# pcb.net
KiCad netlist of a schematic drawn in EAGLE
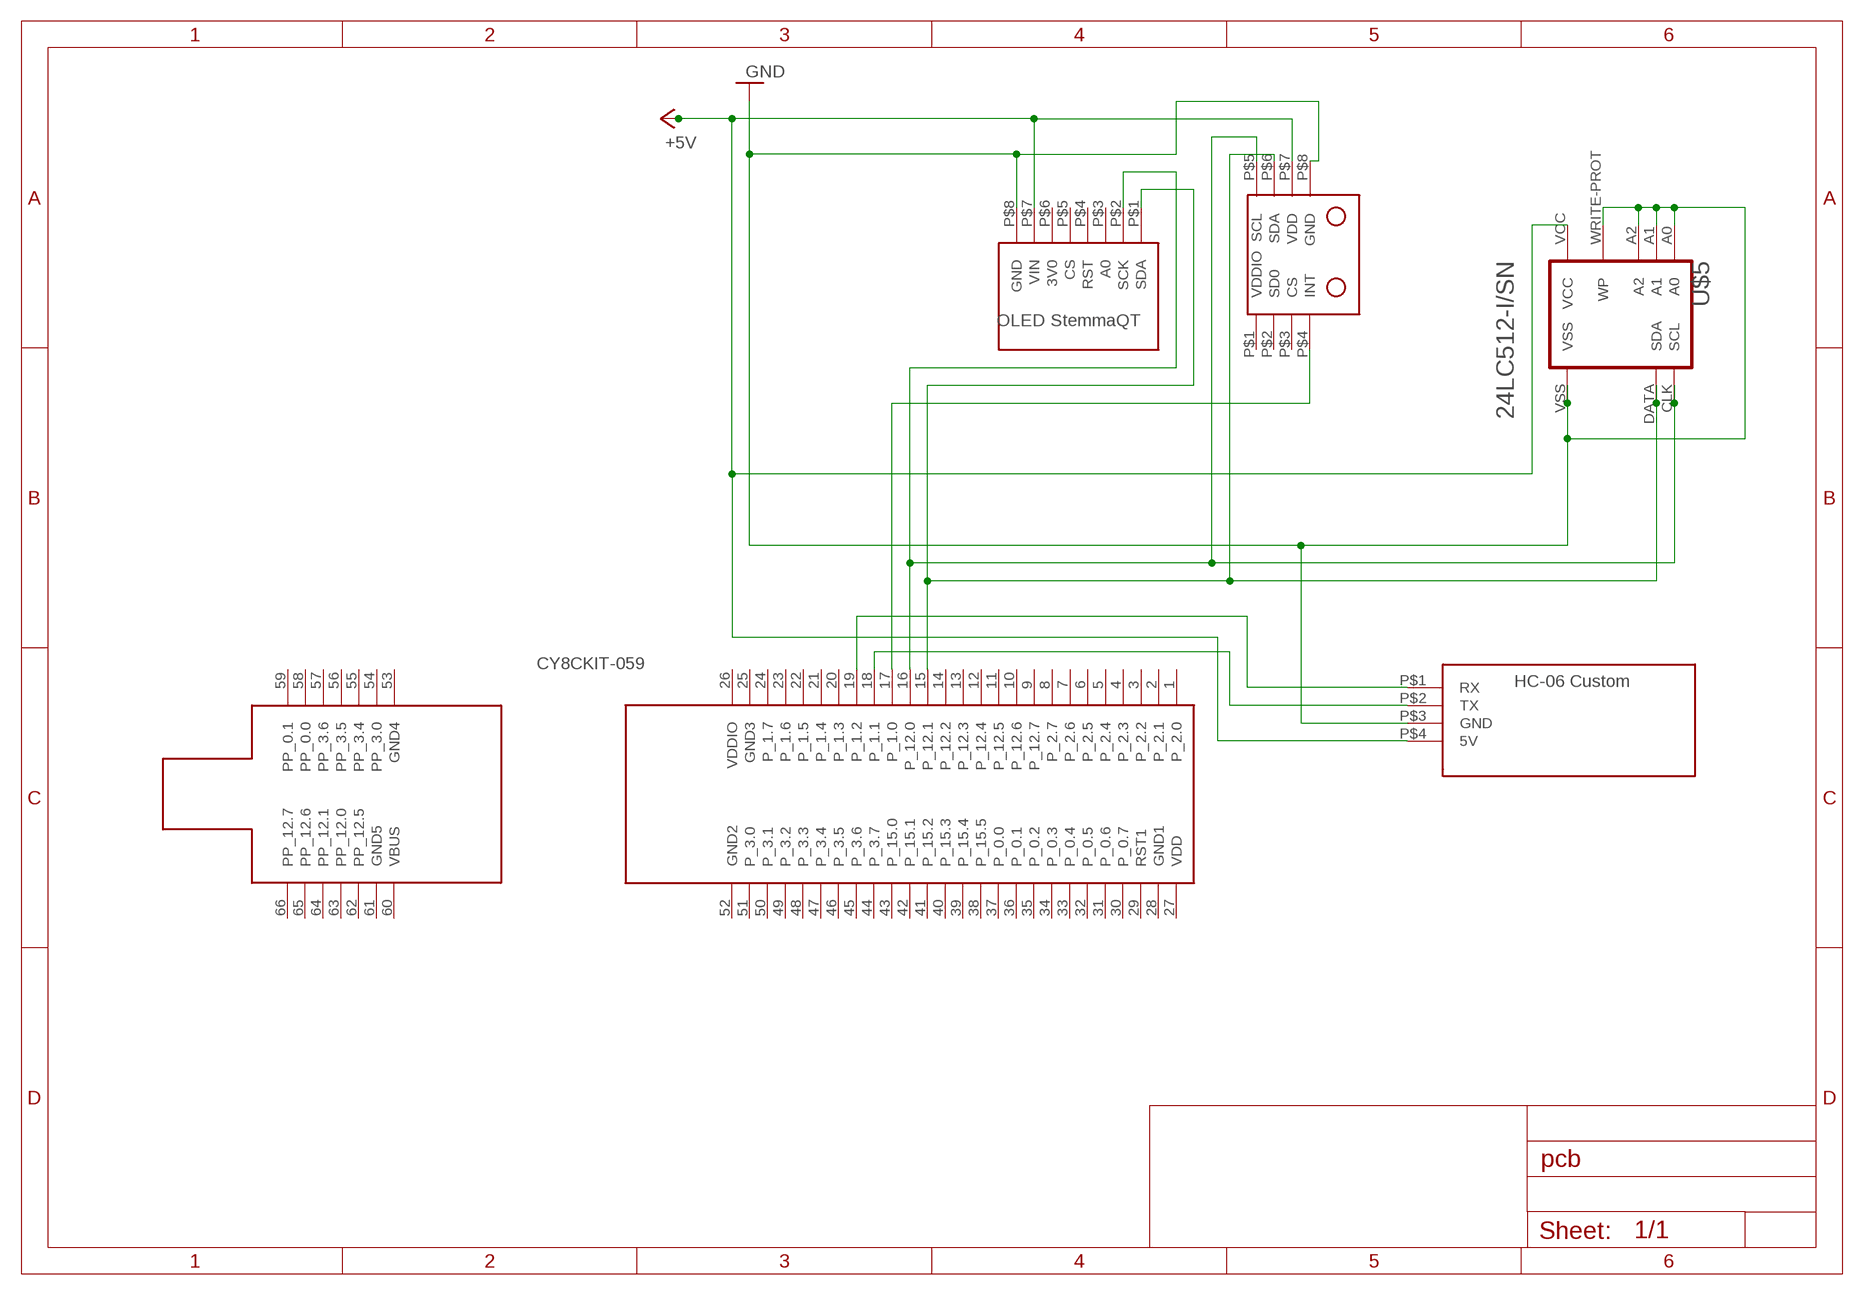
[diagram p0: schematic, sheet 1]

(export (version "E")
  (design (tool "Eeschema 10.0.6"))
  (components
    (comp (ref "U$1")
      (value "CY8CKIT-059")
      (footprint "eagle-import:CY8CKIT-059")
      (libsource (lib "eagle-import") (part "CY8CKIT-059"))
    )
    (comp (ref "U$2")
      (value "SSD1306_STEMMAQT_128X64")
      (footprint "eagle-import:FTP_SSD1306_128X64_4PIN")
      (libsource (lib "eagle-import") (part "SSD1306_STEMMAQT_128X64"))
    )
    (comp (ref "U$3")
      (value "HC-06_CUSTOM")
      (footprint "eagle-import:FTP_HC-06_CUSTOM")
      (libsource (lib "eagle-import") (part "HC-06_CUSTOM"))
    )
    (comp (ref "U$4")
      (value "MPU9250")
      (footprint "eagle-import:FTP_MPU9650")
      (libsource (lib "eagle-import") (part "MPU9250"))
    )
    (comp (ref "U$5")
      (value "24LC512-I-CUSTOM")
      (footprint "eagle-import:24LC512-I-CUSTOM")
      (libsource (lib "eagle-import") (part "24LC512-I-CUSTOM"))
    )
  )
  (nets
    (net (code "1") (name "+5V") (class "Default")
      (node (ref "U$2") (pin "P$7") (pinfunction "VIN_P$7") (pintype "bidirectional"))
      (node (ref "U$3") (pin "P$4") (pinfunction "5V_P$4") (pintype "bidirectional"))
      (node (ref "U$4") (pin "P$7") (pinfunction "VDD_P$7") (pintype "bidirectional"))
      (node (ref "U$5") (pin "VCC") (pinfunction "VCC_VCC") (pintype "power_in"))
    )
    (net (code "2") (name "GND") (class "Default")
      (node (ref "U$2") (pin "P$8") (pinfunction "GND_P$8") (pintype "bidirectional"))
      (node (ref "U$3") (pin "P$3") (pinfunction "GND_P$3") (pintype "bidirectional"))
      (node (ref "U$4") (pin "P$8") (pinfunction "GND_P$8") (pintype "bidirectional"))
      (node (ref "U$5") (pin "A0") (pinfunction "A0_A0") (pintype "input"))
      (node (ref "U$5") (pin "A1") (pinfunction "A1_A1") (pintype "input"))
      (node (ref "U$5") (pin "A2") (pinfunction "A2_A2") (pintype "input"))
      (node (ref "U$5") (pin "VSS") (pinfunction "VSS_VSS") (pintype "power_in"))
      (node (ref "U$5") (pin "WRITE-PROT") (pinfunction "WP_WRITE-PROT") (pintype "input"))
    )
    (net (code "3") (name "Net-(U$1-P_1.0)") (class "Default")
      (node (ref "U$1") (pin "17") (pinfunction "P_1.0_17") (pintype "bidirectional"))
      (node (ref "U$4") (pin "P$4") (pinfunction "INT_P$4") (pintype "bidirectional"))
    )
    (net (code "4") (name "Net-(U$1-P_1.1)") (class "Default")
      (node (ref "U$1") (pin "18") (pinfunction "P_1.1_18") (pintype "bidirectional"))
      (node (ref "U$3") (pin "P$2") (pinfunction "TX_P$2") (pintype "bidirectional"))
    )
    (net (code "5") (name "Net-(U$1-P_1.2)") (class "Default")
      (node (ref "U$1") (pin "19") (pinfunction "P_1.2_19") (pintype "bidirectional"))
      (node (ref "U$3") (pin "P$1") (pinfunction "RX_P$1") (pintype "bidirectional"))
    )
    (net (code "6") (name "Net-(U$1-P_12.0)") (class "Default")
      (node (ref "U$1") (pin "16") (pinfunction "P_12.0_16") (pintype "bidirectional"))
      (node (ref "U$2") (pin "P$2") (pinfunction "SCK_P$2") (pintype "bidirectional"))
      (node (ref "U$4") (pin "P$5") (pinfunction "SCL_P$5") (pintype "bidirectional"))
      (node (ref "U$5") (pin "CLK") (pinfunction "SCL_CLK") (pintype "input"))
    )
    (net (code "7") (name "Net-(U$1-P_12.1)") (class "Default")
      (node (ref "U$1") (pin "15") (pinfunction "P_12.1_15") (pintype "bidirectional"))
      (node (ref "U$2") (pin "P$1") (pinfunction "SDA_P$1") (pintype "bidirectional"))
      (node (ref "U$4") (pin "P$6") (pinfunction "SDA_P$6") (pintype "bidirectional"))
      (node (ref "U$5") (pin "DATA") (pinfunction "SDA_DATA") (pintype "bidirectional"))
    )
    (net (code "8") (name "unconnected-(U$1-GND1-Pad28)") (class "Default")
      (node (ref "U$1") (pin "28") (pinfunction "GND1_28") (pintype "bidirectional"))
    )
    (net (code "9") (name "unconnected-(U$1-GND2-Pad52)") (class "Default")
      (node (ref "U$1") (pin "52") (pinfunction "GND2_52") (pintype "bidirectional"))
    )
    (net (code "10") (name "unconnected-(U$1-GND3-Pad25)") (class "Default")
      (node (ref "U$1") (pin "25") (pinfunction "GND3_25") (pintype "bidirectional"))
    )
    (net (code "11") (name "unconnected-(U$1-GND4-Pad53)") (class "Default")
      (node (ref "U$1") (pin "53") (pinfunction "GND4_53") (pintype "bidirectional"))
    )
    (net (code "12") (name "unconnected-(U$1-GND5-Pad61)") (class "Default")
      (node (ref "U$1") (pin "61") (pinfunction "GND5_61") (pintype "bidirectional"))
    )
    (net (code "13") (name "unconnected-(U$1-PP_0.0-Pad58)") (class "Default")
      (node (ref "U$1") (pin "58") (pinfunction "PP_0.0_58") (pintype "bidirectional"))
    )
    (net (code "14") (name "unconnected-(U$1-PP_0.1-Pad59)") (class "Default")
      (node (ref "U$1") (pin "59") (pinfunction "PP_0.1_59") (pintype "bidirectional"))
    )
    (net (code "15") (name "unconnected-(U$1-PP_3.0-Pad54)") (class "Default")
      (node (ref "U$1") (pin "54") (pinfunction "PP_3.0_54") (pintype "bidirectional"))
    )
    (net (code "16") (name "unconnected-(U$1-PP_3.4-Pad55)") (class "Default")
      (node (ref "U$1") (pin "55") (pinfunction "PP_3.4_55") (pintype "bidirectional"))
    )
    (net (code "17") (name "unconnected-(U$1-PP_3.5-Pad56)") (class "Default")
      (node (ref "U$1") (pin "56") (pinfunction "PP_3.5_56") (pintype "bidirectional"))
    )
    (net (code "18") (name "unconnected-(U$1-PP_3.6-Pad57)") (class "Default")
      (node (ref "U$1") (pin "57") (pinfunction "PP_3.6_57") (pintype "bidirectional"))
    )
    (net (code "19") (name "unconnected-(U$1-PP_12.0-Pad63)") (class "Default")
      (node (ref "U$1") (pin "63") (pinfunction "PP_12.0_63") (pintype "bidirectional"))
    )
    (net (code "20") (name "unconnected-(U$1-PP_12.1-Pad64)") (class "Default")
      (node (ref "U$1") (pin "64") (pinfunction "PP_12.1_64") (pintype "bidirectional"))
    )
    (net (code "21") (name "unconnected-(U$1-PP_12.5-Pad62)") (class "Default")
      (node (ref "U$1") (pin "62") (pinfunction "PP_12.5_62") (pintype "bidirectional"))
    )
    (net (code "22") (name "unconnected-(U$1-PP_12.6-Pad65)") (class "Default")
      (node (ref "U$1") (pin "65") (pinfunction "PP_12.6_65") (pintype "bidirectional"))
    )
    (net (code "23") (name "unconnected-(U$1-PP_12.7-Pad66)") (class "Default")
      (node (ref "U$1") (pin "66") (pinfunction "PP_12.7_66") (pintype "bidirectional"))
    )
    (net (code "24") (name "unconnected-(U$1-P_0.0-Pad37)") (class "Default")
      (node (ref "U$1") (pin "37") (pinfunction "P_0.0_37") (pintype "bidirectional"))
    )
    (net (code "25") (name "unconnected-(U$1-P_0.1-Pad36)") (class "Default")
      (node (ref "U$1") (pin "36") (pinfunction "P_0.1_36") (pintype "bidirectional"))
    )
    (net (code "26") (name "unconnected-(U$1-P_0.2-Pad35)") (class "Default")
      (node (ref "U$1") (pin "35") (pinfunction "P_0.2_35") (pintype "bidirectional"))
    )
    (net (code "27") (name "unconnected-(U$1-P_0.3-Pad34)") (class "Default")
      (node (ref "U$1") (pin "34") (pinfunction "P_0.3_34") (pintype "bidirectional"))
    )
    (net (code "28") (name "unconnected-(U$1-P_0.4-Pad33)") (class "Default")
      (node (ref "U$1") (pin "33") (pinfunction "P_0.4_33") (pintype "bidirectional"))
    )
    (net (code "29") (name "unconnected-(U$1-P_0.5-Pad32)") (class "Default")
      (node (ref "U$1") (pin "32") (pinfunction "P_0.5_32") (pintype "bidirectional"))
    )
    (net (code "30") (name "unconnected-(U$1-P_0.6-Pad31)") (class "Default")
      (node (ref "U$1") (pin "31") (pinfunction "P_0.6_31") (pintype "bidirectional"))
    )
    (net (code "31") (name "unconnected-(U$1-P_0.7-Pad30)") (class "Default")
      (node (ref "U$1") (pin "30") (pinfunction "P_0.7_30") (pintype "bidirectional"))
    )
    (net (code "32") (name "unconnected-(U$1-P_1.3-Pad20)") (class "Default")
      (node (ref "U$1") (pin "20") (pinfunction "P_1.3_20") (pintype "bidirectional"))
    )
    (net (code "33") (name "unconnected-(U$1-P_1.4-Pad21)") (class "Default")
      (node (ref "U$1") (pin "21") (pinfunction "P_1.4_21") (pintype "bidirectional"))
    )
    (net (code "34") (name "unconnected-(U$1-P_1.5-Pad22)") (class "Default")
      (node (ref "U$1") (pin "22") (pinfunction "P_1.5_22") (pintype "bidirectional"))
    )
    (net (code "35") (name "unconnected-(U$1-P_1.6-Pad23)") (class "Default")
      (node (ref "U$1") (pin "23") (pinfunction "P_1.6_23") (pintype "bidirectional"))
    )
    (net (code "36") (name "unconnected-(U$1-P_1.7-Pad24)") (class "Default")
      (node (ref "U$1") (pin "24") (pinfunction "P_1.7_24") (pintype "bidirectional"))
    )
    (net (code "37") (name "unconnected-(U$1-P_2.0-Pad1)") (class "Default")
      (node (ref "U$1") (pin "1") (pinfunction "P_2.0_1") (pintype "bidirectional"))
    )
    (net (code "38") (name "unconnected-(U$1-P_2.1-Pad2)") (class "Default")
      (node (ref "U$1") (pin "2") (pinfunction "P_2.1_2") (pintype "bidirectional"))
    )
    (net (code "39") (name "unconnected-(U$1-P_2.2-Pad3)") (class "Default")
      (node (ref "U$1") (pin "3") (pinfunction "P_2.2_3") (pintype "bidirectional"))
    )
    (net (code "40") (name "unconnected-(U$1-P_2.3-Pad4)") (class "Default")
      (node (ref "U$1") (pin "4") (pinfunction "P_2.3_4") (pintype "bidirectional"))
    )
    (net (code "41") (name "unconnected-(U$1-P_2.4-Pad5)") (class "Default")
      (node (ref "U$1") (pin "5") (pinfunction "P_2.4_5") (pintype "bidirectional"))
    )
    (net (code "42") (name "unconnected-(U$1-P_2.5-Pad6)") (class "Default")
      (node (ref "U$1") (pin "6") (pinfunction "P_2.5_6") (pintype "bidirectional"))
    )
    (net (code "43") (name "unconnected-(U$1-P_2.6-Pad7)") (class "Default")
      (node (ref "U$1") (pin "7") (pinfunction "P_2.6_7") (pintype "bidirectional"))
    )
    (net (code "44") (name "unconnected-(U$1-P_2.7-Pad8)") (class "Default")
      (node (ref "U$1") (pin "8") (pinfunction "P_2.7_8") (pintype "bidirectional"))
    )
    (net (code "45") (name "unconnected-(U$1-P_3.0-Pad51)") (class "Default")
      (node (ref "U$1") (pin "51") (pinfunction "P_3.0_51") (pintype "bidirectional"))
    )
    (net (code "46") (name "unconnected-(U$1-P_3.1-Pad50)") (class "Default")
      (node (ref "U$1") (pin "50") (pinfunction "P_3.1_50") (pintype "bidirectional"))
    )
    (net (code "47") (name "unconnected-(U$1-P_3.2-Pad49)") (class "Default")
      (node (ref "U$1") (pin "49") (pinfunction "P_3.2_49") (pintype "bidirectional"))
    )
    (net (code "48") (name "unconnected-(U$1-P_3.3-Pad48)") (class "Default")
      (node (ref "U$1") (pin "48") (pinfunction "P_3.3_48") (pintype "bidirectional"))
    )
    (net (code "49") (name "unconnected-(U$1-P_3.4-Pad47)") (class "Default")
      (node (ref "U$1") (pin "47") (pinfunction "P_3.4_47") (pintype "bidirectional"))
    )
    (net (code "50") (name "unconnected-(U$1-P_3.5-Pad46)") (class "Default")
      (node (ref "U$1") (pin "46") (pinfunction "P_3.5_46") (pintype "bidirectional"))
    )
    (net (code "51") (name "unconnected-(U$1-P_3.6-Pad45)") (class "Default")
      (node (ref "U$1") (pin "45") (pinfunction "P_3.6_45") (pintype "bidirectional"))
    )
    (net (code "52") (name "unconnected-(U$1-P_3.7-Pad44)") (class "Default")
      (node (ref "U$1") (pin "44") (pinfunction "P_3.7_44") (pintype "bidirectional"))
    )
    (net (code "53") (name "unconnected-(U$1-P_12.2-Pad14)") (class "Default")
      (node (ref "U$1") (pin "14") (pinfunction "P_12.2_14") (pintype "bidirectional"))
    )
    (net (code "54") (name "unconnected-(U$1-P_12.3-Pad13)") (class "Default")
      (node (ref "U$1") (pin "13") (pinfunction "P_12.3_13") (pintype "bidirectional"))
    )
    (net (code "55") (name "unconnected-(U$1-P_12.4-Pad12)") (class "Default")
      (node (ref "U$1") (pin "12") (pinfunction "P_12.4_12") (pintype "bidirectional"))
    )
    (net (code "56") (name "unconnected-(U$1-P_12.5-Pad11)") (class "Default")
      (node (ref "U$1") (pin "11") (pinfunction "P_12.5_11") (pintype "bidirectional"))
    )
    (net (code "57") (name "unconnected-(U$1-P_12.6-Pad10)") (class "Default")
      (node (ref "U$1") (pin "10") (pinfunction "P_12.6_10") (pintype "bidirectional"))
    )
    (net (code "58") (name "unconnected-(U$1-P_12.7-Pad9)") (class "Default")
      (node (ref "U$1") (pin "9") (pinfunction "P_12.7_9") (pintype "bidirectional"))
    )
    (net (code "59") (name "unconnected-(U$1-P_15.0-Pad43)") (class "Default")
      (node (ref "U$1") (pin "43") (pinfunction "P_15.0_43") (pintype "bidirectional"))
    )
    (net (code "60") (name "unconnected-(U$1-P_15.1-Pad42)") (class "Default")
      (node (ref "U$1") (pin "42") (pinfunction "P_15.1_42") (pintype "bidirectional"))
    )
    (net (code "61") (name "unconnected-(U$1-P_15.2-Pad41)") (class "Default")
      (node (ref "U$1") (pin "41") (pinfunction "P_15.2_41") (pintype "bidirectional"))
    )
    (net (code "62") (name "unconnected-(U$1-P_15.3-Pad40)") (class "Default")
      (node (ref "U$1") (pin "40") (pinfunction "P_15.3_40") (pintype "bidirectional"))
    )
    (net (code "63") (name "unconnected-(U$1-P_15.4-Pad39)") (class "Default")
      (node (ref "U$1") (pin "39") (pinfunction "P_15.4_39") (pintype "bidirectional"))
    )
    (net (code "64") (name "unconnected-(U$1-P_15.5-Pad38)") (class "Default")
      (node (ref "U$1") (pin "38") (pinfunction "P_15.5_38") (pintype "bidirectional"))
    )
    (net (code "65") (name "unconnected-(U$1-RST1-Pad29)") (class "Default")
      (node (ref "U$1") (pin "29") (pinfunction "RST1_29") (pintype "bidirectional"))
    )
    (net (code "66") (name "unconnected-(U$1-VBUS-Pad60)") (class "Default")
      (node (ref "U$1") (pin "60") (pinfunction "VBUS_60") (pintype "bidirectional"))
    )
    (net (code "67") (name "unconnected-(U$1-VDD-Pad27)") (class "Default")
      (node (ref "U$1") (pin "27") (pinfunction "VDD_27") (pintype "bidirectional"))
    )
    (net (code "68") (name "unconnected-(U$1-VDDIO-Pad26)") (class "Default")
      (node (ref "U$1") (pin "26") (pinfunction "VDDIO_26") (pintype "bidirectional"))
    )
    (net (code "69") (name "unconnected-(U$2-3V0-PadP$6)") (class "Default")
      (node (ref "U$2") (pin "P$6") (pinfunction "3V0_P$6") (pintype "bidirectional"))
    )
    (net (code "70") (name "unconnected-(U$2-A0-PadP$3)") (class "Default")
      (node (ref "U$2") (pin "P$3") (pinfunction "A0_P$3") (pintype "bidirectional"))
    )
    (net (code "71") (name "unconnected-(U$2-CS-PadP$5)") (class "Default")
      (node (ref "U$2") (pin "P$5") (pinfunction "CS_P$5") (pintype "bidirectional"))
    )
    (net (code "72") (name "unconnected-(U$2-RST-PadP$4)") (class "Default")
      (node (ref "U$2") (pin "P$4") (pinfunction "RST_P$4") (pintype "bidirectional"))
    )
    (net (code "73") (name "unconnected-(U$4-CS-PadP$3)") (class "Default")
      (node (ref "U$4") (pin "P$3") (pinfunction "CS_P$3") (pintype "bidirectional"))
    )
    (net (code "74") (name "unconnected-(U$4-SD0-PadP$2)") (class "Default")
      (node (ref "U$4") (pin "P$2") (pinfunction "SD0_P$2") (pintype "bidirectional"))
    )
    (net (code "75") (name "unconnected-(U$4-VDDIO-PadP$1)") (class "Default")
      (node (ref "U$4") (pin "P$1") (pinfunction "VDDIO_P$1") (pintype "bidirectional"))
    )
  )
)
